# SegmentDisplay.net
KiCad netlist of a schematic drawn in EAGLE
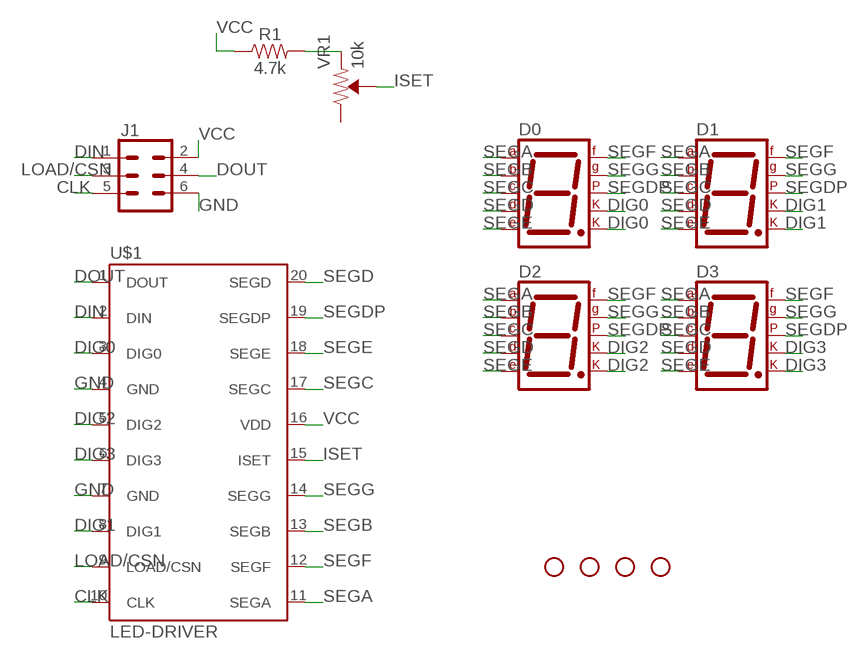
[diagram p0: schematic, sheet 1]

(export (version "E")
  (design (tool "Eeschema 10.0.6"))
  (components
    (comp (ref "D0")
      (value "7SEG-CK")
      (footprint "eagle-import:7SEG-13")
      (libsource (lib "eagle-import") (part "7SEG-CK"))
    )
    (comp (ref "D1")
      (value "7SEG-CK")
      (footprint "eagle-import:7SEG-13")
      (libsource (lib "eagle-import") (part "7SEG-CK"))
    )
    (comp (ref "D2")
      (value "7SEG-CK")
      (footprint "eagle-import:7SEG-13")
      (libsource (lib "eagle-import") (part "7SEG-CK"))
    )
    (comp (ref "D3")
      (value "7SEG-CK")
      (footprint "eagle-import:7SEG-13")
      (libsource (lib "eagle-import") (part "7SEG-CK"))
    )
    (comp (ref "H1")
      (value "STAND-OFF")
      (footprint "eagle-import:STAND-OFF")
      (libsource (lib "eagle-import") (part "STAND-OFF"))
    )
    (comp (ref "H2")
      (value "STAND-OFF")
      (footprint "eagle-import:STAND-OFF")
      (libsource (lib "eagle-import") (part "STAND-OFF"))
    )
    (comp (ref "H3")
      (value "STAND-OFF")
      (footprint "eagle-import:STAND-OFF")
      (libsource (lib "eagle-import") (part "STAND-OFF"))
    )
    (comp (ref "H4")
      (value "STAND-OFF")
      (footprint "eagle-import:STAND-OFF")
      (libsource (lib "eagle-import") (part "STAND-OFF"))
    )
    (comp (ref "J1")
      (value "CONN_03X2NO_SILK")
      (footprint "eagle-import:2X3-NS")
      (libsource (lib "eagle-import") (part "CONN_03X2NO_SILK"))
    )
    (comp (ref "R1")
      (value "4.7k")
      (footprint "eagle-import:0603")
      (libsource (lib "eagle-import") (part "4.7KOHM-0603-1/10W-1%"))
    )
    (comp (ref "U$1")
      (value "LED-DRIVER")
      (footprint "eagle-import:SOIC20L")
      (libsource (lib "eagle-import") (part "LED-DRIVERAS1108LED-DRIVER-SOIC"))
    )
    (comp (ref "VR1")
      (value "10k")
      (footprint "eagle-import:TRIMPOT-PTH-3386U")
      (libsource (lib "eagle-import") (part "TRIMPOT-PTH-10MM-KNOB-1/2W-10%"))
    )
  )
  (nets
    (net (code "1") (name "/CLK") (class "Default")
      (node (ref "J1") (pin "5") (pinfunction "5_5") (pintype "bidirectional"))
      (node (ref "U$1") (pin "10") (pinfunction "CLK_10") (pintype "bidirectional"))
    )
    (net (code "2") (name "/DIG0") (class "Default")
      (node (ref "D0") (pin "3") (pinfunction "CK1_3") (pintype "passive"))
      (node (ref "D0") (pin "8") (pinfunction "CK2_8") (pintype "passive"))
      (node (ref "U$1") (pin "3") (pinfunction "DIG0_3") (pintype "bidirectional"))
    )
    (net (code "3") (name "/DIG1") (class "Default")
      (node (ref "D1") (pin "3") (pinfunction "CK1_3") (pintype "passive"))
      (node (ref "D1") (pin "8") (pinfunction "CK2_8") (pintype "passive"))
      (node (ref "U$1") (pin "8") (pinfunction "DIG1_8") (pintype "bidirectional"))
    )
    (net (code "4") (name "/DIG2") (class "Default")
      (node (ref "D2") (pin "3") (pinfunction "CK1_3") (pintype "passive"))
      (node (ref "D2") (pin "8") (pinfunction "CK2_8") (pintype "passive"))
      (node (ref "U$1") (pin "5") (pinfunction "DIG2_5") (pintype "bidirectional"))
    )
    (net (code "5") (name "/DIG3") (class "Default")
      (node (ref "D3") (pin "3") (pinfunction "CK1_3") (pintype "passive"))
      (node (ref "D3") (pin "8") (pinfunction "CK2_8") (pintype "passive"))
      (node (ref "U$1") (pin "6") (pinfunction "DIG3_6") (pintype "bidirectional"))
    )
    (net (code "6") (name "/DIN") (class "Default")
      (node (ref "J1") (pin "1") (pinfunction "1_1") (pintype "bidirectional"))
      (node (ref "U$1") (pin "2") (pinfunction "DIN_2") (pintype "bidirectional"))
    )
    (net (code "7") (name "/DOUT") (class "Default")
      (node (ref "J1") (pin "4") (pinfunction "4_4") (pintype "bidirectional"))
      (node (ref "U$1") (pin "1") (pinfunction "DOUT_1") (pintype "bidirectional"))
    )
    (net (code "8") (name "/GND") (class "Default")
      (node (ref "J1") (pin "6") (pinfunction "6_6") (pintype "bidirectional"))
      (node (ref "U$1") (pin "4") (pinfunction "GND_4") (pintype "power_in"))
      (node (ref "U$1") (pin "7") (pinfunction "GND_7") (pintype "power_in"))
    )
    (net (code "9") (name "/ISET") (class "Default")
      (node (ref "U$1") (pin "15") (pinfunction "ISET_15") (pintype "bidirectional"))
      (node (ref "VR1") (pin "2") (pinfunction "WIPER_2") (pintype "passive"))
    )
    (net (code "10") (name "/LOAD{slash}CSN") (class "Default")
      (node (ref "J1") (pin "3") (pinfunction "3_3") (pintype "bidirectional"))
      (node (ref "U$1") (pin "9") (pinfunction "LOAD/CSN_9") (pintype "bidirectional"))
    )
    (net (code "11") (name "/SEGA") (class "Default")
      (node (ref "D0") (pin "7") (pinfunction "A_7") (pintype "passive"))
      (node (ref "D1") (pin "7") (pinfunction "A_7") (pintype "passive"))
      (node (ref "D2") (pin "7") (pinfunction "A_7") (pintype "passive"))
      (node (ref "D3") (pin "7") (pinfunction "A_7") (pintype "passive"))
      (node (ref "U$1") (pin "11") (pinfunction "SEGA_11") (pintype "bidirectional"))
    )
    (net (code "12") (name "/SEGB") (class "Default")
      (node (ref "D0") (pin "6") (pinfunction "B_6") (pintype "passive"))
      (node (ref "D1") (pin "6") (pinfunction "B_6") (pintype "passive"))
      (node (ref "D2") (pin "6") (pinfunction "B_6") (pintype "passive"))
      (node (ref "D3") (pin "6") (pinfunction "B_6") (pintype "passive"))
      (node (ref "U$1") (pin "13") (pinfunction "SEGB_13") (pintype "bidirectional"))
    )
    (net (code "13") (name "/SEGC") (class "Default")
      (node (ref "D0") (pin "4") (pinfunction "C_4") (pintype "passive"))
      (node (ref "D1") (pin "4") (pinfunction "C_4") (pintype "passive"))
      (node (ref "D2") (pin "4") (pinfunction "C_4") (pintype "passive"))
      (node (ref "D3") (pin "4") (pinfunction "C_4") (pintype "passive"))
      (node (ref "U$1") (pin "17") (pinfunction "SEGC_17") (pintype "bidirectional"))
    )
    (net (code "14") (name "/SEGD") (class "Default")
      (node (ref "D0") (pin "2") (pinfunction "D_2") (pintype "passive"))
      (node (ref "D1") (pin "2") (pinfunction "D_2") (pintype "passive"))
      (node (ref "D2") (pin "2") (pinfunction "D_2") (pintype "passive"))
      (node (ref "D3") (pin "2") (pinfunction "D_2") (pintype "passive"))
      (node (ref "U$1") (pin "20") (pinfunction "SEGD_20") (pintype "bidirectional"))
    )
    (net (code "15") (name "/SEGDP") (class "Default")
      (node (ref "D0") (pin "5") (pinfunction "DP_5") (pintype "passive"))
      (node (ref "D1") (pin "5") (pinfunction "DP_5") (pintype "passive"))
      (node (ref "D2") (pin "5") (pinfunction "DP_5") (pintype "passive"))
      (node (ref "D3") (pin "5") (pinfunction "DP_5") (pintype "passive"))
      (node (ref "U$1") (pin "19") (pinfunction "SEGDP_19") (pintype "bidirectional"))
    )
    (net (code "16") (name "/SEGE") (class "Default")
      (node (ref "D0") (pin "1") (pinfunction "E_1") (pintype "passive"))
      (node (ref "D1") (pin "1") (pinfunction "E_1") (pintype "passive"))
      (node (ref "D2") (pin "1") (pinfunction "E_1") (pintype "passive"))
      (node (ref "D3") (pin "1") (pinfunction "E_1") (pintype "passive"))
      (node (ref "U$1") (pin "18") (pinfunction "SEGE_18") (pintype "bidirectional"))
    )
    (net (code "17") (name "/SEGF") (class "Default")
      (node (ref "D0") (pin "9") (pinfunction "F_9") (pintype "passive"))
      (node (ref "D1") (pin "9") (pinfunction "F_9") (pintype "passive"))
      (node (ref "D2") (pin "9") (pinfunction "F_9") (pintype "passive"))
      (node (ref "D3") (pin "9") (pinfunction "F_9") (pintype "passive"))
      (node (ref "U$1") (pin "12") (pinfunction "SEGF_12") (pintype "bidirectional"))
    )
    (net (code "18") (name "/SEGG") (class "Default")
      (node (ref "D0") (pin "10") (pinfunction "G_10") (pintype "passive"))
      (node (ref "D1") (pin "10") (pinfunction "G_10") (pintype "passive"))
      (node (ref "D2") (pin "10") (pinfunction "G_10") (pintype "passive"))
      (node (ref "D3") (pin "10") (pinfunction "G_10") (pintype "passive"))
      (node (ref "U$1") (pin "14") (pinfunction "SEGG_14") (pintype "bidirectional"))
    )
    (net (code "19") (name "/VCC") (class "Default")
      (node (ref "J1") (pin "2") (pinfunction "2_2") (pintype "bidirectional"))
      (node (ref "R1") (pin "1") (pinfunction "1_1") (pintype "passive"))
      (node (ref "U$1") (pin "16") (pinfunction "VDD_16") (pintype "power_in"))
    )
    (net (code "20") (name "Net-(VR1-CCW)") (class "Default")
      (node (ref "R1") (pin "2") (pinfunction "2_2") (pintype "passive"))
      (node (ref "VR1") (pin "1") (pinfunction "CCW_1") (pintype "passive"))
    )
    (net (code "21") (name "unconnected-(VR1-CW-Pad3)") (class "Default")
      (node (ref "VR1") (pin "3") (pinfunction "CW_3") (pintype "passive"))
    )
  )
)
